# controltemperature.net
KiCad netlist of a schematic drawn in Altium Designer
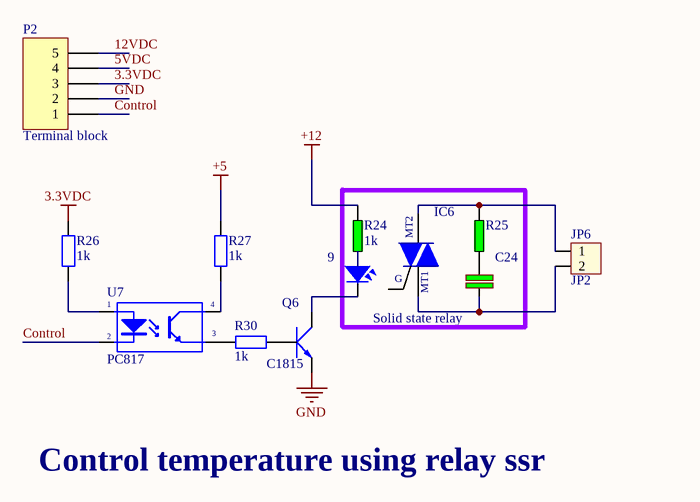
[diagram p0: controltemperature.SchDoc]

(export (version "E")
  (design (tool "Eeschema 10.0.6"))
  (components
    (comp (ref "9")
      (value "Solid state relay")
      (footprint "LED-3")
      (description "LED Single colour Green and Red")
      (libsource (lib "My Library") (part "LED"))
    )
    (comp (ref "C24")
      (value "~")
      (footprint "heromap:CN1")
      (description "Cap np  1pF - 472pF")
      (libsource (lib "My Library") (part "CAP"))
    )
    (comp (ref "IC6")
      (value "~")
      (footprint "QTO-220")
      (description "Triacs - 8A")
      (libsource (lib "My Library") (part "BT137"))
    )
    (comp (ref "JP6")
      (value "JP2")
      (footprint "CON2")
      (description "Connector 2")
      (libsource (lib "My Library") (part "Con2"))
    )
    (comp (ref "P2")
      (value "Terminal block")
      (footprint "HDR1X5")
      (description "Header, 5-Pin")
      (fields (field (name "PUBLISHER") "Altium Limited"))
      (libsource (lib "My Library") (part "Header 5"))
    )
    (comp (ref "Q6")
      (value "C1815")
      (footprint "QTO-92")
      (description "NPN 600mW, ECB")
      (libsource (lib "syhaunguyen") (part "C1815"))
    )
    (comp (ref "R24")
      (value "1k")
      (footprint "heromap:SM-1206")
      (description "Resistor 1/4W")
      (libsource (lib "My Library") (part "RES"))
    )
    (comp (ref "R25")
      (value "~")
      (footprint "heromap:SM-1206")
      (description "Resistor 1/4W")
      (libsource (lib "My Library") (part "RES"))
    )
    (comp (ref "R26")
      (value "1k")
      (footprint "R1/4W")
      (description "Resistor 1/4W")
      (libsource (lib "syhaunguyen") (part "R1/4W"))
    )
    (comp (ref "R27")
      (value "1k")
      (footprint "R1/4W")
      (description "Resistor 1/4W")
      (libsource (lib "syhaunguyen") (part "R1/4W"))
    )
    (comp (ref "R30")
      (value "1k")
      (footprint "R1/4W")
      (description "Resistor 1/4W")
      (libsource (lib "syhaunguyen") (part "R1/4W"))
    )
    (comp (ref "U7")
      (value "PC817")
      (footprint "DIP4/W0.3")
      (description "Single Opto")
      (libsource (lib "My Library") (part "PC817"))
    )
  )
  (nets
    (net (code "1") (name "+5") (class "Default")
      (node (ref "R27") (pin "2") (pinfunction "2_2") (pintype "passive"))
    )
    (net (code "2") (name "+12") (class "Default")
      (node (ref "R24") (pin "2") (pinfunction "2_2") (pintype "passive"))
    )
    (net (code "3") (name "/5VDC") (class "Default")
      (node (ref "P2") (pin "4") (pinfunction "4_4") (pintype "passive"))
    )
    (net (code "4") (name "/12VDC") (class "Default")
      (node (ref "P2") (pin "5") (pinfunction "5_5") (pintype "passive"))
    )
    (net (code "5") (name "/Control") (class "Default")
      (node (ref "P2") (pin "1") (pinfunction "1_1") (pintype "passive"))
      (node (ref "U7") (pin "2") (pinfunction "K_2") (pintype "passive"))
    )
    (net (code "6") (name "3.3VDC") (class "Default")
      (node (ref "P2") (pin "3") (pinfunction "3_3") (pintype "passive"))
      (node (ref "R26") (pin "2") (pinfunction "2_2") (pintype "passive"))
    )
    (net (code "7") (name "GND") (class "Default")
      (node (ref "P2") (pin "2") (pinfunction "2_2") (pintype "passive"))
      (node (ref "Q6") (pin "1") (pinfunction "E_1") (pintype "passive"))
    )
    (net (code "8") (name "Net-(9-Pad1)") (class "Default")
      (node (ref "9") (pin "1") (pinfunction "1_1") (pintype "passive"))
      (node (ref "R24") (pin "1") (pinfunction "1_1") (pintype "passive"))
    )
    (net (code "9") (name "Net-(C24-Pad2)") (class "Default")
      (node (ref "C24") (pin "2") (pinfunction "2_2") (pintype "passive"))
      (node (ref "R25") (pin "1") (pinfunction "1_1") (pintype "passive"))
    )
    (net (code "10") (name "Net-(IC6-MT1)") (class "Default")
      (node (ref "C24") (pin "1") (pinfunction "1_1") (pintype "passive"))
      (node (ref "IC6") (pin "1") (pinfunction "MT1_1") (pintype "passive"))
      (node (ref "JP6") (pin "2") (pinfunction "2_2") (pintype "passive"))
    )
    (net (code "11") (name "Net-(IC6-MT2)") (class "Default")
      (node (ref "IC6") (pin "2") (pinfunction "MT2_2") (pintype "passive"))
      (node (ref "JP6") (pin "1") (pinfunction "1_1") (pintype "passive"))
      (node (ref "R25") (pin "2") (pinfunction "2_2") (pintype "passive"))
    )
    (net (code "12") (name "Net-(Q6-B)") (class "Default")
      (node (ref "Q6") (pin "3") (pinfunction "B_3") (pintype "passive"))
      (node (ref "R30") (pin "2") (pinfunction "2_2") (pintype "passive"))
    )
    (net (code "13") (name "Net-(Q6-C)") (class "Default")
      (node (ref "9") (pin "2") (pinfunction "2_2") (pintype "passive"))
      (node (ref "Q6") (pin "2") (pinfunction "C_2") (pintype "passive"))
    )
    (net (code "14") (name "Net-(U7-A)") (class "Default")
      (node (ref "R26") (pin "1") (pinfunction "1_1") (pintype "passive"))
      (node (ref "U7") (pin "1") (pinfunction "A_1") (pintype "passive"))
    )
    (net (code "15") (name "Net-(U7-C)") (class "Default")
      (node (ref "R27") (pin "1") (pinfunction "1_1") (pintype "passive"))
      (node (ref "U7") (pin "4") (pinfunction "C_4") (pintype "passive"))
    )
    (net (code "16") (name "Net-(U7-E)") (class "Default")
      (node (ref "R30") (pin "1") (pinfunction "1_1") (pintype "passive"))
      (node (ref "U7") (pin "3") (pinfunction "E_3") (pintype "passive"))
    )
    (net (code "17") (name "unconnected-(IC6-IN-Pad3)") (class "Default")
      (node (ref "IC6") (pin "3") (pinfunction "IN_3") (pintype "passive"))
    )
  )
)
